# Kube-Module-OLED_AmbiMate.net
KiCad netlist of a schematic drawn in EAGLE
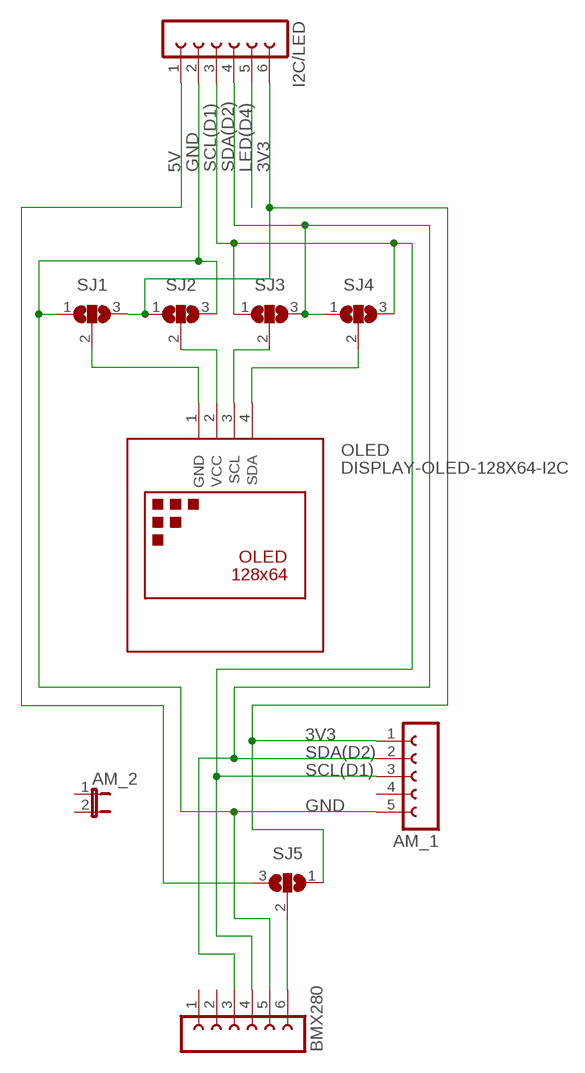
[diagram p0: schematic, sheet 1]

(export (version "E")
  (design (tool "Eeschema 10.0.6"))
  (components
    (comp (ref "AM_1")
      (value "FE05-1")
      (footprint "eagle-import:FE05-1")
      (libsource (lib "eagle-import") (part "FE05-1"))
    )
    (comp (ref "AM_2")
      (value "JP1E")
      (footprint "eagle-import:JP1")
      (libsource (lib "eagle-import") (part "JP1E"))
    )
    (comp (ref "BMX280")
      (value "FE06-1")
      (footprint "eagle-import:FE06")
      (libsource (lib "eagle-import") (part "FE06-1"))
    )
    (comp (ref "I2C/LED")
      (value "FE06-1")
      (footprint "eagle-import:FE06")
      (libsource (lib "eagle-import") (part "FE06-1"))
    )
    (comp (ref "OLED")
      (value "DISPLAY-OLED-128X64-I2C")
      (footprint "eagle-import:DISPLAY-OLED-128X64-I2C")
      (libsource (lib "eagle-import") (part "DISPLAY-OLED-128X64-I2C"))
    )
    (comp (ref "SJ1")
      (value "SJ2W")
      (footprint "eagle-import:SJ_2")
      (libsource (lib "eagle-import") (part "SJ2W"))
    )
    (comp (ref "SJ2")
      (value "SJ2W")
      (footprint "eagle-import:SJ_2")
      (libsource (lib "eagle-import") (part "SJ2W"))
    )
    (comp (ref "SJ3")
      (value "SJ2W")
      (footprint "eagle-import:SJ_2")
      (libsource (lib "eagle-import") (part "SJ2W"))
    )
    (comp (ref "SJ4")
      (value "SJ2W")
      (footprint "eagle-import:SJ_2")
      (libsource (lib "eagle-import") (part "SJ2W"))
    )
    (comp (ref "SJ5")
      (value "SJ2W")
      (footprint "eagle-import:SJ_2")
      (libsource (lib "eagle-import") (part "SJ2W"))
    )
  )
  (nets
    (net (code "1") (name "/3V3") (class "Default")
      (node (ref "AM_1") (pin "1") (pinfunction "1_1") (pintype "passive"))
      (node (ref "I2C/LED") (pin "6") (pinfunction "6_6") (pintype "passive"))
      (node (ref "SJ1") (pin "3") (pinfunction "3_3") (pintype "passive"))
      (node (ref "SJ2") (pin "1") (pinfunction "1_1") (pintype "passive"))
      (node (ref "SJ5") (pin "1") (pinfunction "1_1") (pintype "passive"))
    )
    (net (code "2") (name "/5V") (class "Default")
      (node (ref "I2C/LED") (pin "1") (pinfunction "1_1") (pintype "passive"))
      (node (ref "SJ5") (pin "3") (pinfunction "3_3") (pintype "passive"))
    )
    (net (code "3") (name "/GND") (class "Default")
      (node (ref "AM_1") (pin "5") (pinfunction "5_5") (pintype "passive"))
      (node (ref "BMX280") (pin "5") (pinfunction "5_5") (pintype "passive"))
      (node (ref "I2C/LED") (pin "2") (pinfunction "2_2") (pintype "passive"))
      (node (ref "SJ1") (pin "1") (pinfunction "1_1") (pintype "passive"))
      (node (ref "SJ2") (pin "3") (pinfunction "3_3") (pintype "passive"))
    )
    (net (code "4") (name "/LED(D4)") (class "Default")
      (node (ref "I2C/LED") (pin "5") (pinfunction "5_5") (pintype "passive"))
    )
    (net (code "5") (name "/SCL(D1)") (class "Default")
      (node (ref "AM_1") (pin "3") (pinfunction "3_3") (pintype "passive"))
      (node (ref "BMX280") (pin "4") (pinfunction "4_4") (pintype "passive"))
      (node (ref "I2C/LED") (pin "3") (pinfunction "3_3") (pintype "passive"))
      (node (ref "SJ3") (pin "1") (pinfunction "1_1") (pintype "passive"))
      (node (ref "SJ4") (pin "3") (pinfunction "3_3") (pintype "passive"))
    )
    (net (code "6") (name "/SDA(D2)") (class "Default")
      (node (ref "AM_1") (pin "2") (pinfunction "2_2") (pintype "passive"))
      (node (ref "BMX280") (pin "3") (pinfunction "3_3") (pintype "passive"))
      (node (ref "I2C/LED") (pin "4") (pinfunction "4_4") (pintype "passive"))
      (node (ref "SJ3") (pin "3") (pinfunction "3_3") (pintype "passive"))
      (node (ref "SJ4") (pin "1") (pinfunction "1_1") (pintype "passive"))
    )
    (net (code "7") (name "Net-(BMX280-Pad6)") (class "Default")
      (node (ref "BMX280") (pin "6") (pinfunction "6_6") (pintype "passive"))
      (node (ref "SJ5") (pin "2") (pinfunction "2_2") (pintype "passive"))
    )
    (net (code "8") (name "Net-(OLED-GND)") (class "Default")
      (node (ref "OLED") (pin "1") (pinfunction "GND_1") (pintype "power_in"))
      (node (ref "SJ1") (pin "2") (pinfunction "2_2") (pintype "passive"))
    )
    (net (code "9") (name "Net-(OLED-SCL)") (class "Default")
      (node (ref "OLED") (pin "3") (pinfunction "SCL_3") (pintype "bidirectional"))
      (node (ref "SJ3") (pin "2") (pinfunction "2_2") (pintype "passive"))
    )
    (net (code "10") (name "Net-(OLED-SDA)") (class "Default")
      (node (ref "OLED") (pin "4") (pinfunction "SDA_4") (pintype "bidirectional"))
      (node (ref "SJ4") (pin "2") (pinfunction "2_2") (pintype "passive"))
    )
    (net (code "11") (name "Net-(OLED-VCC)") (class "Default")
      (node (ref "OLED") (pin "2") (pinfunction "VCC_2") (pintype "power_in"))
      (node (ref "SJ2") (pin "2") (pinfunction "2_2") (pintype "passive"))
    )
    (net (code "12") (name "unconnected-(AM_1-Pad4)") (class "Default")
      (node (ref "AM_1") (pin "4") (pinfunction "4_4") (pintype "passive"))
    )
    (net (code "13") (name "unconnected-(AM_2-Pad1)") (class "Default")
      (node (ref "AM_2") (pin "1") (pinfunction "1_1") (pintype "passive"))
    )
    (net (code "14") (name "unconnected-(AM_2-Pad2)") (class "Default")
      (node (ref "AM_2") (pin "2") (pinfunction "2_2") (pintype "passive"))
    )
    (net (code "15") (name "unconnected-(BMX280-Pad1)") (class "Default")
      (node (ref "BMX280") (pin "1") (pinfunction "1_1") (pintype "passive"))
    )
    (net (code "16") (name "unconnected-(BMX280-Pad2)") (class "Default")
      (node (ref "BMX280") (pin "2") (pinfunction "2_2") (pintype "passive"))
    )
  )
)
